# Shield.net
KiCad netlist of a schematic drawn in EAGLE
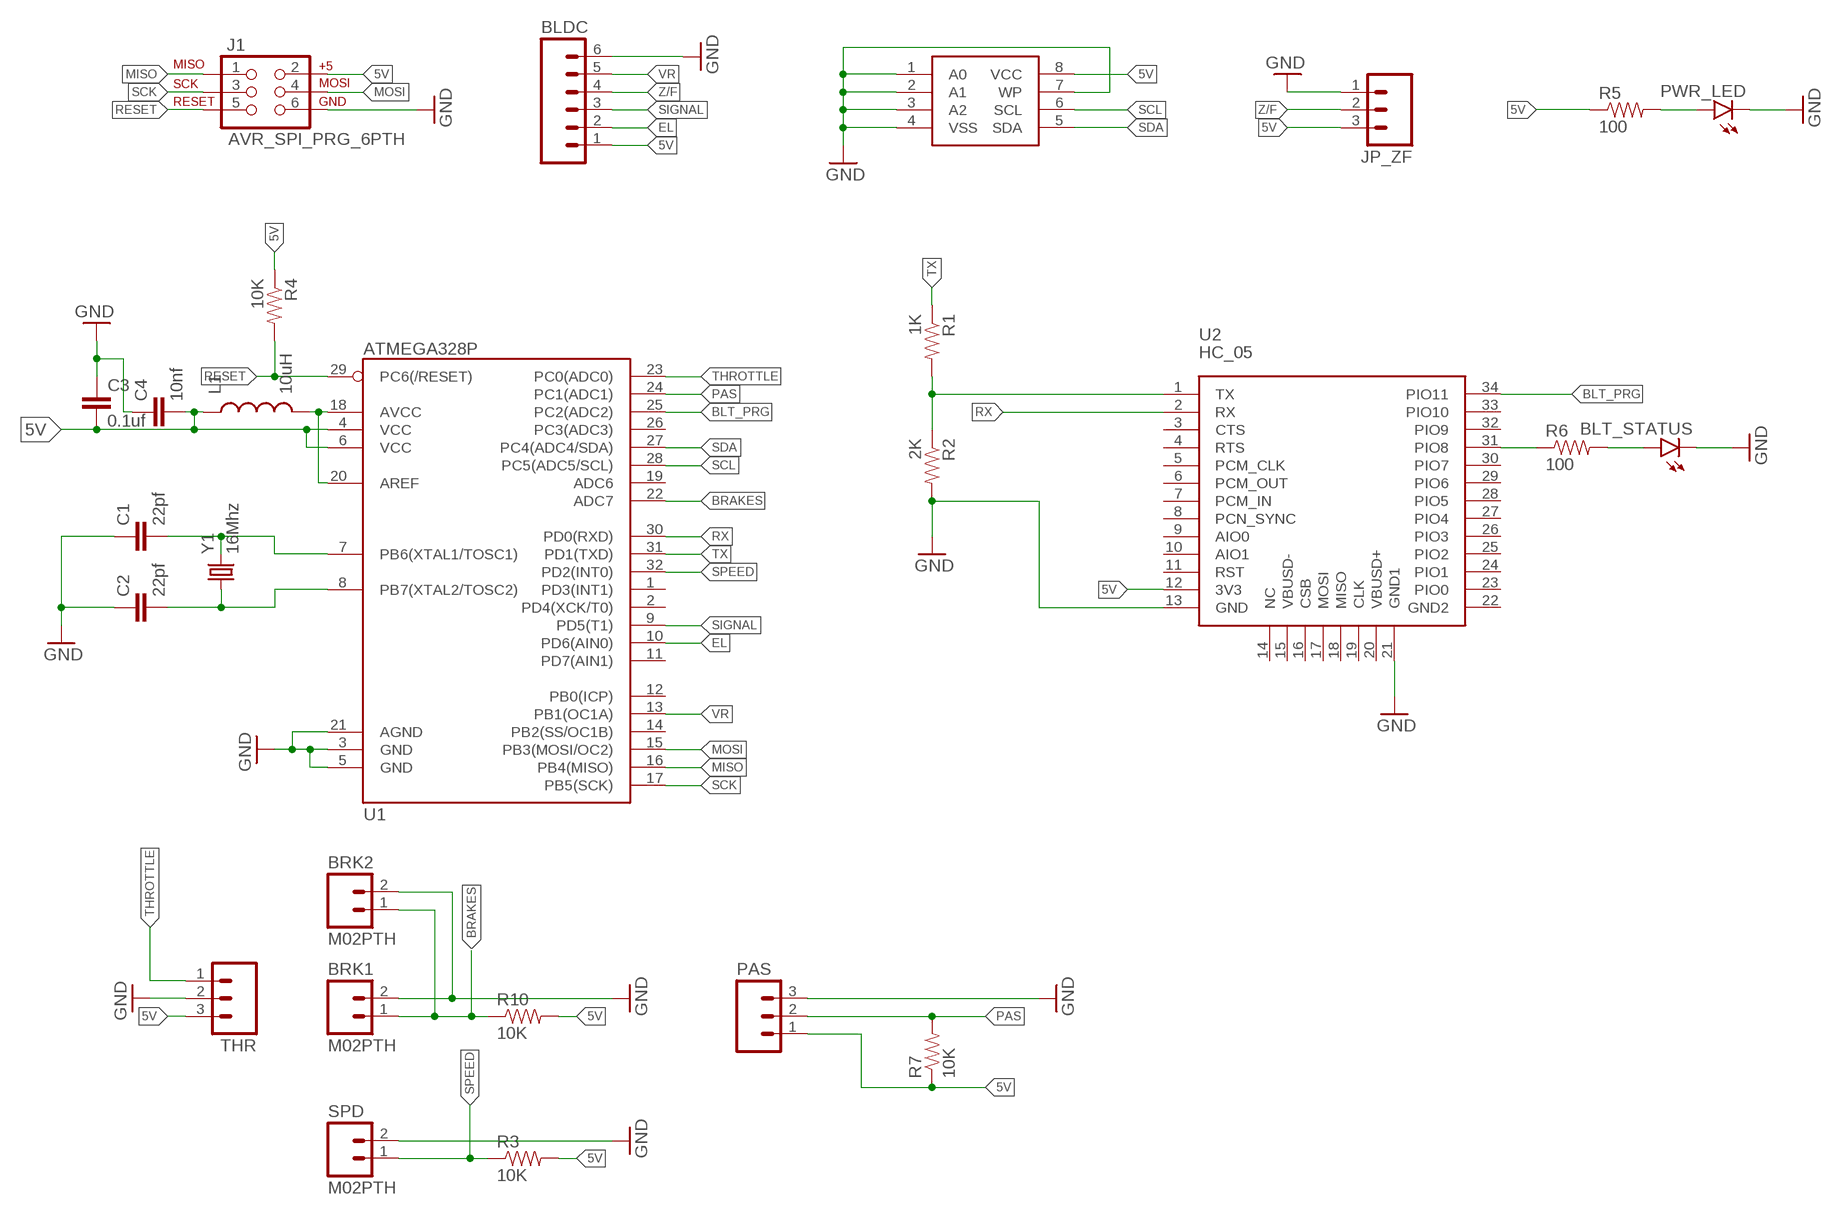
[diagram p0: schematic, sheet 1]

(export (version "E")
  (design (tool "Eeschema 10.0.6"))
  (components
    (comp (ref "BLDC")
      (value "M06NO_SILK_FEMALE_PTH")
      (footprint "eagle-import:1X06_NO_SILK")
      (libsource (lib "eagle-import") (part "M06NO_SILK_FEMALE_PTH"))
    )
    (comp (ref "BLT_STATUS")
      (value "LED1206")
      (footprint "eagle-import:LED-1206")
      (libsource (lib "eagle-import") (part "LED1206"))
    )
    (comp (ref "BRK1")
      (value "M02PTH")
      (footprint "eagle-import:1X02")
      (libsource (lib "eagle-import") (part "M02PTH"))
    )
    (comp (ref "BRK2")
      (value "M02PTH")
      (footprint "eagle-import:1X02")
      (libsource (lib "eagle-import") (part "M02PTH"))
    )
    (comp (ref "C1")
      (value "22pf")
      (footprint "eagle-import:1206")
      (libsource (lib "eagle-import") (part "CAP1206"))
    )
    (comp (ref "C2")
      (value "22pf")
      (footprint "eagle-import:1206")
      (libsource (lib "eagle-import") (part "CAP1206"))
    )
    (comp (ref "C3")
      (value "0.1uf")
      (footprint "eagle-import:1206")
      (libsource (lib "eagle-import") (part "CAP1206"))
    )
    (comp (ref "C4")
      (value "10nf")
      (footprint "eagle-import:1206")
      (libsource (lib "eagle-import") (part "CAP1206"))
    )
    (comp (ref "J1")
      (value "AVR_SPI_PRG_6PTH")
      (footprint "eagle-import:2X3")
      (libsource (lib "eagle-import") (part "AVR_SPI_PRG_6PTH"))
    )
    (comp (ref "JP_ZF")
      (value "M03PTH")
      (footprint "eagle-import:1X03")
      (libsource (lib "eagle-import") (part "M03PTH"))
    )
    (comp (ref "L1")
      (value "10uH")
      (footprint "eagle-import:0805")
      (libsource (lib "eagle-import") (part "INDUCTOR0805"))
    )
    (comp (ref "PAS")
      (value "M03PTH")
      (footprint "eagle-import:1X03")
      (libsource (lib "eagle-import") (part "M03PTH"))
    )
    (comp (ref "PWR_LED")
      (value "LED1206")
      (footprint "eagle-import:LED-1206")
      (libsource (lib "eagle-import") (part "LED1206"))
    )
    (comp (ref "R1")
      (value "1K")
      (footprint "eagle-import:1206")
      (libsource (lib "eagle-import") (part "RESISTOR1206"))
    )
    (comp (ref "R2")
      (value "2K")
      (footprint "eagle-import:1206")
      (libsource (lib "eagle-import") (part "RESISTOR1206"))
    )
    (comp (ref "R3")
      (value "10K")
      (footprint "eagle-import:1206")
      (libsource (lib "eagle-import") (part "RESISTOR1206"))
    )
    (comp (ref "R4")
      (value "10K")
      (footprint "eagle-import:1206")
      (libsource (lib "eagle-import") (part "RESISTOR1206"))
    )
    (comp (ref "R5")
      (value "100")
      (footprint "eagle-import:1206")
      (libsource (lib "eagle-import") (part "RESISTOR1206"))
    )
    (comp (ref "R6")
      (value "100")
      (footprint "eagle-import:1206")
      (libsource (lib "eagle-import") (part "RESISTOR1206"))
    )
    (comp (ref "R7")
      (value "10K")
      (footprint "eagle-import:1206")
      (libsource (lib "eagle-import") (part "RESISTOR1206"))
    )
    (comp (ref "R10")
      (value "10K")
      (footprint "eagle-import:1206")
      (libsource (lib "eagle-import") (part "RESISTOR1206"))
    )
    (comp (ref "SPD")
      (value "M02PTH")
      (footprint "eagle-import:1X02")
      (libsource (lib "eagle-import") (part "M02PTH"))
    )
    (comp (ref "THR")
      (value "M03PTH")
      (footprint "eagle-import:1X03")
      (libsource (lib "eagle-import") (part "M03PTH"))
    )
    (comp (ref "U$2")
      (value "24AAXXX")
      (footprint "eagle-import:SOIC-8-EIAJ")
      (libsource (lib "eagle-import") (part "24AAXXX"))
    )
    (comp (ref "U1")
      (value "ATMEGA328P")
      (footprint "eagle-import:TQFP32-08")
      (libsource (lib "eagle-import") (part "ATMEGA328_SMT"))
    )
    (comp (ref "U2")
      (value "HC_05")
      (footprint "eagle-import:BLUETOOTH_SMD")
      (libsource (lib "eagle-import") (part "HC_05"))
    )
    (comp (ref "Y1")
      (value "16Mhz")
      (footprint "eagle-import:HC49US")
      (libsource (lib "eagle-import") (part "CRYSTALHC49US"))
    )
  )
  (nets
    (net (code "1") (name "5V") (class "Default")
      (node (ref "BLDC") (pin "1") (pinfunction "1_1") (pintype "passive"))
      (node (ref "C3") (pin "2") (pinfunction "2_2") (pintype "passive"))
      (node (ref "C4") (pin "2") (pinfunction "2_2") (pintype "passive"))
      (node (ref "J1") (pin "2") (pinfunction "2_2") (pintype "passive"))
      (node (ref "JP_ZF") (pin "3") (pinfunction "3_3") (pintype "passive"))
      (node (ref "L1") (pin "1") (pinfunction "1_1") (pintype "passive"))
      (node (ref "PAS") (pin "1") (pinfunction "1_1") (pintype "passive"))
      (node (ref "R10") (pin "2") (pinfunction "2_2") (pintype "passive"))
      (node (ref "R3") (pin "2") (pinfunction "2_2") (pintype "passive"))
      (node (ref "R4") (pin "1") (pinfunction "1_1") (pintype "passive"))
      (node (ref "R5") (pin "1") (pinfunction "1_1") (pintype "passive"))
      (node (ref "R7") (pin "1") (pinfunction "1_1") (pintype "passive"))
      (node (ref "THR") (pin "3") (pinfunction "3_3") (pintype "passive"))
      (node (ref "U$2") (pin "8") (pinfunction "VCC_8") (pintype "bidirectional"))
      (node (ref "U1") (pin "4") (pinfunction "VCC_4") (pintype "bidirectional"))
      (node (ref "U1") (pin "6") (pinfunction "VCC_6") (pintype "bidirectional"))
      (node (ref "U2") (pin "12") (pinfunction "3V3_12") (pintype "bidirectional"))
    )
    (net (code "2") (name "BLT_PRG") (class "Default")
      (node (ref "U1") (pin "25") (pinfunction "PC2(ADC2)_25") (pintype "bidirectional"))
      (node (ref "U2") (pin "34") (pinfunction "PIO11_34") (pintype "bidirectional"))
    )
    (net (code "3") (name "BRAKES") (class "Default")
      (node (ref "BRK1") (pin "1") (pinfunction "1_1") (pintype "passive"))
      (node (ref "BRK2") (pin "1") (pinfunction "1_1") (pintype "passive"))
      (node (ref "R10") (pin "1") (pinfunction "1_1") (pintype "passive"))
      (node (ref "U1") (pin "22") (pinfunction "ADC7_22") (pintype "bidirectional"))
    )
    (net (code "4") (name "EL") (class "Default")
      (node (ref "BLDC") (pin "2") (pinfunction "2_2") (pintype "passive"))
      (node (ref "U1") (pin "10") (pinfunction "PD6(AIN0)_10") (pintype "bidirectional"))
    )
    (net (code "5") (name "GND") (class "Default")
      (node (ref "BLDC") (pin "6") (pinfunction "6_6") (pintype "passive"))
      (node (ref "BLT_STATUS") (pin "C") (pinfunction "C_C") (pintype "passive"))
      (node (ref "BRK1") (pin "2") (pinfunction "2_2") (pintype "passive"))
      (node (ref "BRK2") (pin "2") (pinfunction "2_2") (pintype "passive"))
      (node (ref "C1") (pin "1") (pinfunction "1_1") (pintype "passive"))
      (node (ref "C2") (pin "1") (pinfunction "1_1") (pintype "passive"))
      (node (ref "C3") (pin "1") (pinfunction "1_1") (pintype "passive"))
      (node (ref "C4") (pin "1") (pinfunction "1_1") (pintype "passive"))
      (node (ref "J1") (pin "6") (pinfunction "6_6") (pintype "passive"))
      (node (ref "JP_ZF") (pin "1") (pinfunction "1_1") (pintype "passive"))
      (node (ref "PAS") (pin "3") (pinfunction "3_3") (pintype "passive"))
      (node (ref "PWR_LED") (pin "C") (pinfunction "C_C") (pintype "passive"))
      (node (ref "R2") (pin "2") (pinfunction "2_2") (pintype "passive"))
      (node (ref "SPD") (pin "2") (pinfunction "2_2") (pintype "passive"))
      (node (ref "THR") (pin "2") (pinfunction "2_2") (pintype "passive"))
      (node (ref "U$2") (pin "1") (pinfunction "A0_1") (pintype "bidirectional"))
      (node (ref "U$2") (pin "2") (pinfunction "A1_2") (pintype "bidirectional"))
      (node (ref "U$2") (pin "3") (pinfunction "A2_3") (pintype "bidirectional"))
      (node (ref "U$2") (pin "4") (pinfunction "VSS_4") (pintype "bidirectional"))
      (node (ref "U$2") (pin "7") (pinfunction "WP_7") (pintype "bidirectional"))
      (node (ref "U1") (pin "21") (pinfunction "AGND_21") (pintype "bidirectional"))
      (node (ref "U1") (pin "3") (pinfunction "GND_3") (pintype "bidirectional"))
      (node (ref "U1") (pin "5") (pinfunction "GND_5") (pintype "bidirectional"))
      (node (ref "U2") (pin "13") (pinfunction "GND_13") (pintype "bidirectional"))
      (node (ref "U2") (pin "21") (pinfunction "GND1_21") (pintype "bidirectional"))
    )
    (net (code "6") (name "MISO") (class "Default")
      (node (ref "J1") (pin "1") (pinfunction "1_1") (pintype "passive"))
      (node (ref "U1") (pin "16") (pinfunction "PB4(MISO)_16") (pintype "bidirectional"))
    )
    (net (code "7") (name "MOSI") (class "Default")
      (node (ref "J1") (pin "4") (pinfunction "4_4") (pintype "passive"))
      (node (ref "U1") (pin "15") (pinfunction "PB3(MOSI/OC2)_15") (pintype "bidirectional"))
    )
    (net (code "8") (name "Net-(BLT_STATUS-PadA)") (class "Default")
      (node (ref "BLT_STATUS") (pin "A") (pinfunction "A_A") (pintype "passive"))
      (node (ref "R6") (pin "2") (pinfunction "2_2") (pintype "passive"))
    )
    (net (code "9") (name "Net-(PWR_LED-PadA)") (class "Default")
      (node (ref "PWR_LED") (pin "A") (pinfunction "A_A") (pintype "passive"))
      (node (ref "R5") (pin "2") (pinfunction "2_2") (pintype "passive"))
    )
    (net (code "10") (name "Net-(U1-AREF)") (class "Default")
      (node (ref "L1") (pin "2") (pinfunction "2_2") (pintype "passive"))
      (node (ref "U1") (pin "18") (pinfunction "AVCC_18") (pintype "bidirectional"))
      (node (ref "U1") (pin "20") (pinfunction "AREF_20") (pintype "bidirectional"))
    )
    (net (code "11") (name "Net-(U1-PB6(XTAL1{slash}TOSC1))") (class "Default")
      (node (ref "C1") (pin "2") (pinfunction "2_2") (pintype "passive"))
      (node (ref "U1") (pin "7") (pinfunction "PB6(XTAL1/TOSC1)_7") (pintype "bidirectional"))
      (node (ref "Y1") (pin "2") (pinfunction "2_2") (pintype "passive"))
    )
    (net (code "12") (name "Net-(U1-PB7(XTAL2{slash}TOSC2))") (class "Default")
      (node (ref "C2") (pin "2") (pinfunction "2_2") (pintype "passive"))
      (node (ref "U1") (pin "8") (pinfunction "PB7(XTAL2/TOSC2)_8") (pintype "bidirectional"))
      (node (ref "Y1") (pin "1") (pinfunction "1_1") (pintype "passive"))
    )
    (net (code "13") (name "Net-(U2-PIO8)") (class "Default")
      (node (ref "R6") (pin "1") (pinfunction "1_1") (pintype "passive"))
      (node (ref "U2") (pin "31") (pinfunction "PIO8_31") (pintype "bidirectional"))
    )
    (net (code "14") (name "Net-(U2-TX)") (class "Default")
      (node (ref "R1") (pin "2") (pinfunction "2_2") (pintype "passive"))
      (node (ref "R2") (pin "1") (pinfunction "1_1") (pintype "passive"))
      (node (ref "U2") (pin "1") (pinfunction "TX_1") (pintype "bidirectional"))
    )
    (net (code "15") (name "PAS") (class "Default")
      (node (ref "PAS") (pin "2") (pinfunction "2_2") (pintype "passive"))
      (node (ref "R7") (pin "2") (pinfunction "2_2") (pintype "passive"))
      (node (ref "U1") (pin "24") (pinfunction "PC1(ADC1)_24") (pintype "bidirectional"))
    )
    (net (code "16") (name "RESET") (class "Default")
      (node (ref "J1") (pin "5") (pinfunction "5_5") (pintype "passive"))
      (node (ref "R4") (pin "2") (pinfunction "2_2") (pintype "passive"))
      (node (ref "U1") (pin "29") (pinfunction "PC6(/RESET)_29") (pintype "bidirectional"))
    )
    (net (code "17") (name "RX") (class "Default")
      (node (ref "U1") (pin "30") (pinfunction "PD0(RXD)_30") (pintype "bidirectional"))
      (node (ref "U2") (pin "2") (pinfunction "RX_2") (pintype "bidirectional"))
    )
    (net (code "18") (name "SCK") (class "Default")
      (node (ref "J1") (pin "3") (pinfunction "3_3") (pintype "passive"))
      (node (ref "U1") (pin "17") (pinfunction "PB5(SCK)_17") (pintype "bidirectional"))
    )
    (net (code "19") (name "SCL") (class "Default")
      (node (ref "U$2") (pin "6") (pinfunction "SCL_6") (pintype "bidirectional"))
      (node (ref "U1") (pin "28") (pinfunction "PC5(ADC5/SCL)_28") (pintype "bidirectional"))
    )
    (net (code "20") (name "SDA") (class "Default")
      (node (ref "U$2") (pin "5") (pinfunction "SDA_5") (pintype "bidirectional"))
      (node (ref "U1") (pin "27") (pinfunction "PC4(ADC4/SDA)_27") (pintype "bidirectional"))
    )
    (net (code "21") (name "SIGNAL") (class "Default")
      (node (ref "BLDC") (pin "3") (pinfunction "3_3") (pintype "passive"))
      (node (ref "U1") (pin "9") (pinfunction "PD5(T1)_9") (pintype "bidirectional"))
    )
    (net (code "22") (name "SPEED") (class "Default")
      (node (ref "R3") (pin "1") (pinfunction "1_1") (pintype "passive"))
      (node (ref "SPD") (pin "1") (pinfunction "1_1") (pintype "passive"))
      (node (ref "U1") (pin "32") (pinfunction "PD2(INT0)_32") (pintype "bidirectional"))
    )
    (net (code "23") (name "THROTTLE") (class "Default")
      (node (ref "THR") (pin "1") (pinfunction "1_1") (pintype "passive"))
      (node (ref "U1") (pin "23") (pinfunction "PC0(ADC0)_23") (pintype "bidirectional"))
    )
    (net (code "24") (name "TX") (class "Default")
      (node (ref "R1") (pin "1") (pinfunction "1_1") (pintype "passive"))
      (node (ref "U1") (pin "31") (pinfunction "PD1(TXD)_31") (pintype "bidirectional"))
    )
    (net (code "25") (name "VR") (class "Default")
      (node (ref "BLDC") (pin "5") (pinfunction "5_5") (pintype "passive"))
      (node (ref "U1") (pin "13") (pinfunction "PB1(OC1A)_13") (pintype "bidirectional"))
    )
    (net (code "26") (name "Z{slash}F") (class "Default")
      (node (ref "BLDC") (pin "4") (pinfunction "4_4") (pintype "passive"))
      (node (ref "JP_ZF") (pin "2") (pinfunction "2_2") (pintype "passive"))
    )
    (net (code "27") (name "unconnected-(U1-ADC6-Pad19)") (class "Default")
      (node (ref "U1") (pin "19") (pinfunction "ADC6_19") (pintype "bidirectional"))
    )
    (net (code "28") (name "unconnected-(U1-PB0(ICP)-Pad12)") (class "Default")
      (node (ref "U1") (pin "12") (pinfunction "PB0(ICP)_12") (pintype "bidirectional"))
    )
    (net (code "29") (name "unconnected-(U1-PB2(SS{slash}OC1B)-Pad14)") (class "Default")
      (node (ref "U1") (pin "14") (pinfunction "PB2(SS/OC1B)_14") (pintype "bidirectional"))
    )
    (net (code "30") (name "unconnected-(U1-PC3(ADC3)-Pad26)") (class "Default")
      (node (ref "U1") (pin "26") (pinfunction "PC3(ADC3)_26") (pintype "bidirectional"))
    )
    (net (code "31") (name "unconnected-(U1-PD3(INT1)-Pad1)") (class "Default")
      (node (ref "U1") (pin "1") (pinfunction "PD3(INT1)_1") (pintype "bidirectional"))
    )
    (net (code "32") (name "unconnected-(U1-PD4(XCK{slash}T0)-Pad2)") (class "Default")
      (node (ref "U1") (pin "2") (pinfunction "PD4(XCK/T0)_2") (pintype "bidirectional"))
    )
    (net (code "33") (name "unconnected-(U1-PD7(AIN1)-Pad11)") (class "Default")
      (node (ref "U1") (pin "11") (pinfunction "PD7(AIN1)_11") (pintype "bidirectional"))
    )
    (net (code "34") (name "unconnected-(U2-AIO0-Pad9)") (class "Default")
      (node (ref "U2") (pin "9") (pinfunction "AIO0_9") (pintype "bidirectional"))
    )
    (net (code "35") (name "unconnected-(U2-AIO1-Pad10)") (class "Default")
      (node (ref "U2") (pin "10") (pinfunction "AIO1_10") (pintype "bidirectional"))
    )
    (net (code "36") (name "unconnected-(U2-CLK-Pad19)") (class "Default")
      (node (ref "U2") (pin "19") (pinfunction "CLK_19") (pintype "bidirectional"))
    )
    (net (code "37") (name "unconnected-(U2-CSB-Pad16)") (class "Default")
      (node (ref "U2") (pin "16") (pinfunction "CSB_16") (pintype "bidirectional"))
    )
    (net (code "38") (name "unconnected-(U2-CTS-Pad3)") (class "Default")
      (node (ref "U2") (pin "3") (pinfunction "CTS_3") (pintype "bidirectional"))
    )
    (net (code "39") (name "unconnected-(U2-GND2-Pad22)") (class "Default")
      (node (ref "U2") (pin "22") (pinfunction "GND2_22") (pintype "bidirectional"))
    )
    (net (code "40") (name "unconnected-(U2-MISO-Pad18)") (class "Default")
      (node (ref "U2") (pin "18") (pinfunction "MISO_18") (pintype "bidirectional"))
    )
    (net (code "41") (name "unconnected-(U2-MOSI-Pad17)") (class "Default")
      (node (ref "U2") (pin "17") (pinfunction "MOSI_17") (pintype "bidirectional"))
    )
    (net (code "42") (name "unconnected-(U2-NC-Pad14)") (class "Default")
      (node (ref "U2") (pin "14") (pinfunction "NC_14") (pintype "bidirectional"))
    )
    (net (code "43") (name "unconnected-(U2-PCM_CLK-Pad5)") (class "Default")
      (node (ref "U2") (pin "5") (pinfunction "PCM_CLK_5") (pintype "bidirectional"))
    )
    (net (code "44") (name "unconnected-(U2-PCM_IN-Pad7)") (class "Default")
      (node (ref "U2") (pin "7") (pinfunction "PCM_IN_7") (pintype "bidirectional"))
    )
    (net (code "45") (name "unconnected-(U2-PCM_OUT-Pad6)") (class "Default")
      (node (ref "U2") (pin "6") (pinfunction "PCM_OUT_6") (pintype "bidirectional"))
    )
    (net (code "46") (name "unconnected-(U2-PCN_SYNC-Pad8)") (class "Default")
      (node (ref "U2") (pin "8") (pinfunction "PCN_SYNC_8") (pintype "bidirectional"))
    )
    (net (code "47") (name "unconnected-(U2-PIO0-Pad23)") (class "Default")
      (node (ref "U2") (pin "23") (pinfunction "PIO0_23") (pintype "bidirectional"))
    )
    (net (code "48") (name "unconnected-(U2-PIO1-Pad24)") (class "Default")
      (node (ref "U2") (pin "24") (pinfunction "PIO1_24") (pintype "bidirectional"))
    )
    (net (code "49") (name "unconnected-(U2-PIO2-Pad25)") (class "Default")
      (node (ref "U2") (pin "25") (pinfunction "PIO2_25") (pintype "bidirectional"))
    )
    (net (code "50") (name "unconnected-(U2-PIO3-Pad26)") (class "Default")
      (node (ref "U2") (pin "26") (pinfunction "PIO3_26") (pintype "bidirectional"))
    )
    (net (code "51") (name "unconnected-(U2-PIO4-Pad27)") (class "Default")
      (node (ref "U2") (pin "27") (pinfunction "PIO4_27") (pintype "bidirectional"))
    )
    (net (code "52") (name "unconnected-(U2-PIO5-Pad28)") (class "Default")
      (node (ref "U2") (pin "28") (pinfunction "PIO5_28") (pintype "bidirectional"))
    )
    (net (code "53") (name "unconnected-(U2-PIO6-Pad29)") (class "Default")
      (node (ref "U2") (pin "29") (pinfunction "PIO6_29") (pintype "bidirectional"))
    )
    (net (code "54") (name "unconnected-(U2-PIO7-Pad30)") (class "Default")
      (node (ref "U2") (pin "30") (pinfunction "PIO7_30") (pintype "bidirectional"))
    )
    (net (code "55") (name "unconnected-(U2-PIO9-Pad32)") (class "Default")
      (node (ref "U2") (pin "32") (pinfunction "PIO9_32") (pintype "bidirectional"))
    )
    (net (code "56") (name "unconnected-(U2-PIO10-Pad33)") (class "Default")
      (node (ref "U2") (pin "33") (pinfunction "PIO10_33") (pintype "bidirectional"))
    )
    (net (code "57") (name "unconnected-(U2-RST-Pad11)") (class "Default")
      (node (ref "U2") (pin "11") (pinfunction "RST_11") (pintype "bidirectional"))
    )
    (net (code "58") (name "unconnected-(U2-RTS-Pad4)") (class "Default")
      (node (ref "U2") (pin "4") (pinfunction "RTS_4") (pintype "bidirectional"))
    )
    (net (code "59") (name "unconnected-(U2-VBUSD+-Pad20)") (class "Default")
      (node (ref "U2") (pin "20") (pinfunction "VBUSD+_20") (pintype "bidirectional"))
    )
    (net (code "60") (name "unconnected-(U2-VBUSD--Pad15)") (class "Default")
      (node (ref "U2") (pin "15") (pinfunction "VBUSD-_15") (pintype "bidirectional"))
    )
  )
)
